# WFT0420CZ15_conv.net
KiCad netlist of a schematic drawn in EAGLE
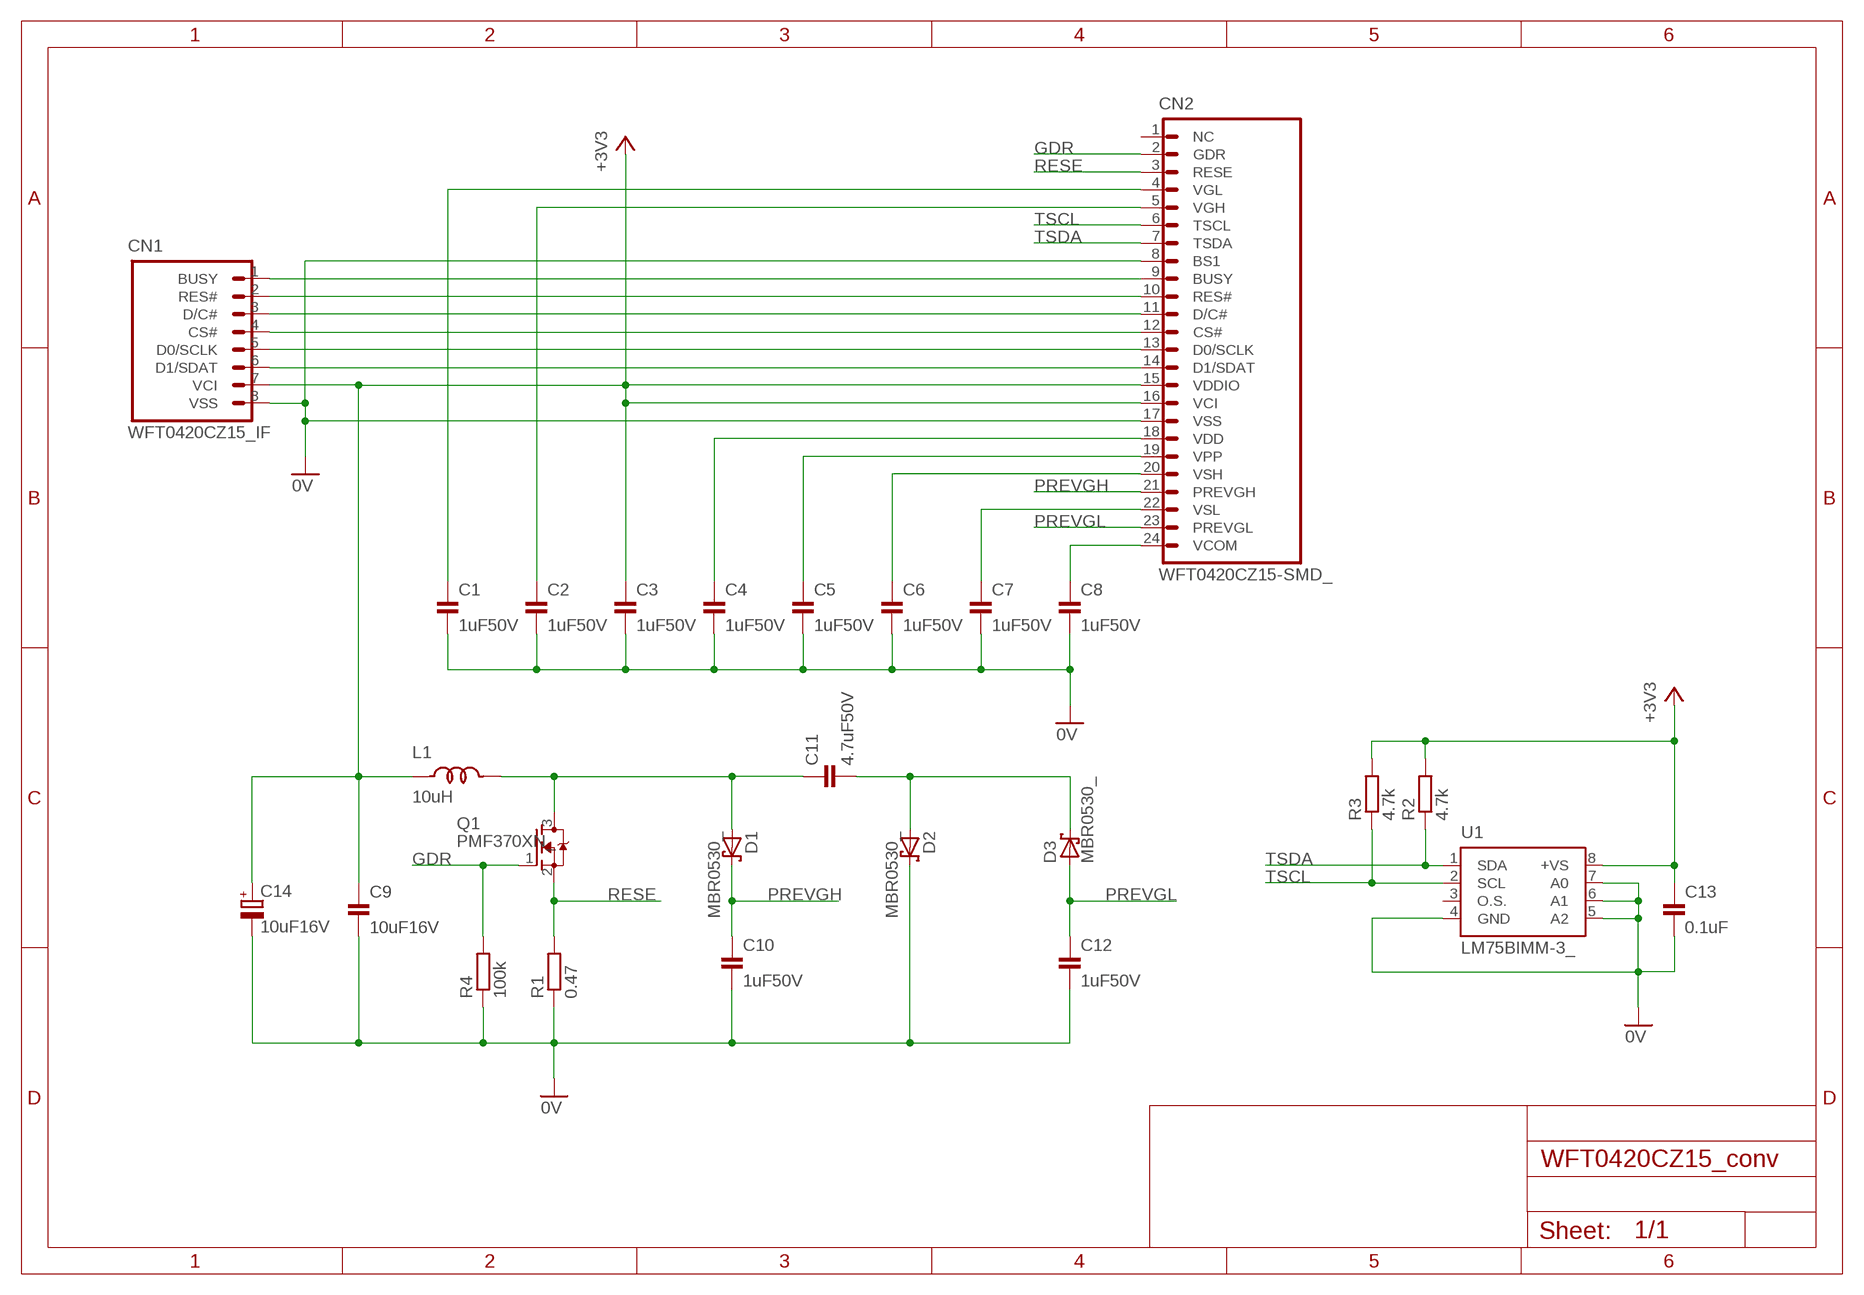
[diagram p0: schematic, sheet 1]

(export (version "E")
  (design (tool "Eeschema 10.0.6"))
  (components
    (comp (ref "C1")
      (value "1uF50V")
      (footprint "eagle-import:SMD_2012")
      (libsource (lib "eagle-import") (part "CAP_0805"))
    )
    (comp (ref "C2")
      (value "1uF50V")
      (footprint "eagle-import:SMD_2012")
      (libsource (lib "eagle-import") (part "CAP_0805"))
    )
    (comp (ref "C3")
      (value "1uF50V")
      (footprint "eagle-import:SMD_2012")
      (libsource (lib "eagle-import") (part "CAP_0805"))
    )
    (comp (ref "C4")
      (value "1uF50V")
      (footprint "eagle-import:SMD_2012")
      (libsource (lib "eagle-import") (part "CAP_0805"))
    )
    (comp (ref "C5")
      (value "1uF50V")
      (footprint "eagle-import:SMD_2012")
      (libsource (lib "eagle-import") (part "CAP_0805"))
    )
    (comp (ref "C6")
      (value "1uF50V")
      (footprint "eagle-import:SMD_2012")
      (libsource (lib "eagle-import") (part "CAP_0805"))
    )
    (comp (ref "C7")
      (value "1uF50V")
      (footprint "eagle-import:SMD_2012")
      (libsource (lib "eagle-import") (part "CAP_0805"))
    )
    (comp (ref "C8")
      (value "1uF50V")
      (footprint "eagle-import:SMD_2012")
      (libsource (lib "eagle-import") (part "CAP_0805"))
    )
    (comp (ref "C9")
      (value "10uF16V")
      (footprint "eagle-import:SMD_2012")
      (libsource (lib "eagle-import") (part "CAP_0805"))
    )
    (comp (ref "C10")
      (value "1uF50V")
      (footprint "eagle-import:SMD_2012")
      (libsource (lib "eagle-import") (part "CAP_0805"))
    )
    (comp (ref "C11")
      (value "4.7uF50V")
      (footprint "eagle-import:SMD_2012")
      (libsource (lib "eagle-import") (part "CAP_0805"))
    )
    (comp (ref "C12")
      (value "1uF50V")
      (footprint "eagle-import:SMD_2012")
      (libsource (lib "eagle-import") (part "CAP_0805"))
    )
    (comp (ref "C13")
      (value "0.1uF")
      (footprint "eagle-import:SMD_2012")
      (libsource (lib "eagle-import") (part "CAP_0805"))
    )
    (comp (ref "C14")
      (value "10uF16V")
      (footprint "eagle-import:C1210_TPST")
      (libsource (lib "eagle-import") (part "TPST106K016R0800"))
    )
    (comp (ref "CN1")
      (value "WFT0420CZ15_IF")
      (footprint "eagle-import:WFT0420CZ15_IF_8PIN")
      (libsource (lib "eagle-import") (part "WFT0420CZ15_IF"))
    )
    (comp (ref "CN2")
      (value "WFT0420CZ15-SMD_")
      (footprint "eagle-import:FH12A-24S-0.5SH_DEV")
      (libsource (lib "eagle-import") (part "WFT0420CZ15-SMD_"))
    )
    (comp (ref "D1")
      (value "MBR0530_")
      (footprint "eagle-import:MBR0530_DEV")
      (libsource (lib "eagle-import") (part "MBR0530_"))
    )
    (comp (ref "D2")
      (value "MBR0530_")
      (footprint "eagle-import:MBR0530_DEV")
      (libsource (lib "eagle-import") (part "MBR0530_"))
    )
    (comp (ref "D3")
      (value "MBR0530_")
      (footprint "eagle-import:MBR0530_DEV")
      (libsource (lib "eagle-import") (part "MBR0530_"))
    )
    (comp (ref "L1")
      (value "10uH")
      (footprint "eagle-import:NLCV25T")
      (libsource (lib "eagle-import") (part "NLCV25T"))
    )
    (comp (ref "Q1")
      (value "PMF370XN_")
      (footprint "eagle-import:SOT323_DEV")
      (libsource (lib "eagle-import") (part "PMF370XN_"))
    )
    (comp (ref "R1")
      (value "0.47")
      (footprint "eagle-import:SMD_2012")
      (libsource (lib "eagle-import") (part "RESISTOR_0805"))
    )
    (comp (ref "R2")
      (value "4.7k")
      (footprint "eagle-import:SMD_2012")
      (libsource (lib "eagle-import") (part "RESISTOR_0805"))
    )
    (comp (ref "R3")
      (value "4.7k")
      (footprint "eagle-import:SMD_2012")
      (libsource (lib "eagle-import") (part "RESISTOR_0805"))
    )
    (comp (ref "R4")
      (value "100k")
      (footprint "eagle-import:SMD_2012")
      (libsource (lib "eagle-import") (part "RESISTOR_0805"))
    )
    (comp (ref "U1")
      (value "LM75BIMM-3_")
      (footprint "eagle-import:SSOP8-DGK_DEV")
      (libsource (lib "eagle-import") (part "LM75BIMM-3_"))
    )
  )
  (nets
    (net (code "1") (name "+3V3") (class "Default")
      (node (ref "C13") (pin "1") (pinfunction "1_1") (pintype "passive"))
      (node (ref "C14") (pin "1") (pinfunction "+_1") (pintype "passive"))
      (node (ref "C3") (pin "1") (pinfunction "1_1") (pintype "passive"))
      (node (ref "C9") (pin "1") (pinfunction "1_1") (pintype "passive"))
      (node (ref "CN1") (pin "7") (pinfunction "VCI_7") (pintype "passive"))
      (node (ref "CN2") (pin "15") (pinfunction "VDDIO_15") (pintype "passive"))
      (node (ref "CN2") (pin "16") (pinfunction "VCI_16") (pintype "passive"))
      (node (ref "L1") (pin "1") (pinfunction "1_1") (pintype "passive"))
      (node (ref "R2") (pin "2") (pinfunction "2_2") (pintype "passive"))
      (node (ref "R3") (pin "2") (pinfunction "2_2") (pintype "passive"))
      (node (ref "U1") (pin "8") (pinfunction "+VS_8") (pintype "passive"))
    )
    (net (code "2") (name "/GDR") (class "Default")
      (node (ref "CN2") (pin "2") (pinfunction "GDR_2") (pintype "bidirectional"))
      (node (ref "Q1") (pin "1") (pinfunction "G_1") (pintype "passive"))
      (node (ref "R4") (pin "2") (pinfunction "2_2") (pintype "passive"))
    )
    (net (code "3") (name "/PREVGH") (class "Default")
      (node (ref "C10") (pin "1") (pinfunction "1_1") (pintype "passive"))
      (node (ref "CN2") (pin "21") (pinfunction "PREVGH_21") (pintype "passive"))
      (node (ref "D1") (pin "1") (pinfunction "C_1") (pintype "passive"))
    )
    (net (code "4") (name "/PREVGL") (class "Default")
      (node (ref "C12") (pin "1") (pinfunction "1_1") (pintype "passive"))
      (node (ref "CN2") (pin "23") (pinfunction "PREVGL_23") (pintype "passive"))
      (node (ref "D3") (pin "2") (pinfunction "A_2") (pintype "passive"))
    )
    (net (code "5") (name "/RESE") (class "Default")
      (node (ref "CN2") (pin "3") (pinfunction "RESE_3") (pintype "bidirectional"))
      (node (ref "Q1") (pin "2") (pinfunction "S_2") (pintype "passive"))
      (node (ref "R1") (pin "2") (pinfunction "2_2") (pintype "passive"))
    )
    (net (code "6") (name "/TSCL") (class "Default")
      (node (ref "CN2") (pin "6") (pinfunction "TSCL_6") (pintype "bidirectional"))
      (node (ref "R3") (pin "1") (pinfunction "1_1") (pintype "passive"))
      (node (ref "U1") (pin "2") (pinfunction "SCL_2") (pintype "bidirectional"))
    )
    (net (code "7") (name "/TSDA") (class "Default")
      (node (ref "CN2") (pin "7") (pinfunction "TSDA_7") (pintype "bidirectional"))
      (node (ref "R2") (pin "1") (pinfunction "1_1") (pintype "passive"))
      (node (ref "U1") (pin "1") (pinfunction "SDA_1") (pintype "bidirectional"))
    )
    (net (code "8") (name "0V") (class "Default")
      (node (ref "C1") (pin "2") (pinfunction "2_2") (pintype "passive"))
      (node (ref "C10") (pin "2") (pinfunction "2_2") (pintype "passive"))
      (node (ref "C12") (pin "2") (pinfunction "2_2") (pintype "passive"))
      (node (ref "C13") (pin "2") (pinfunction "2_2") (pintype "passive"))
      (node (ref "C14") (pin "2") (pinfunction "-_2") (pintype "passive"))
      (node (ref "C2") (pin "2") (pinfunction "2_2") (pintype "passive"))
      (node (ref "C3") (pin "2") (pinfunction "2_2") (pintype "passive"))
      (node (ref "C4") (pin "2") (pinfunction "2_2") (pintype "passive"))
      (node (ref "C5") (pin "2") (pinfunction "2_2") (pintype "passive"))
      (node (ref "C6") (pin "2") (pinfunction "2_2") (pintype "passive"))
      (node (ref "C7") (pin "2") (pinfunction "2_2") (pintype "passive"))
      (node (ref "C8") (pin "2") (pinfunction "2_2") (pintype "passive"))
      (node (ref "C9") (pin "2") (pinfunction "2_2") (pintype "passive"))
      (node (ref "CN1") (pin "8") (pinfunction "VSS_8") (pintype "passive"))
      (node (ref "CN2") (pin "17") (pinfunction "VSS_17") (pintype "passive"))
      (node (ref "CN2") (pin "8") (pinfunction "BS1_8") (pintype "bidirectional"))
      (node (ref "D2") (pin "1") (pinfunction "C_1") (pintype "passive"))
      (node (ref "R1") (pin "1") (pinfunction "1_1") (pintype "passive"))
      (node (ref "R4") (pin "1") (pinfunction "1_1") (pintype "passive"))
      (node (ref "U1") (pin "4") (pinfunction "GND_4") (pintype "passive"))
      (node (ref "U1") (pin "5") (pinfunction "A2_5") (pintype "bidirectional"))
      (node (ref "U1") (pin "6") (pinfunction "A1_6") (pintype "bidirectional"))
      (node (ref "U1") (pin "7") (pinfunction "A0_7") (pintype "bidirectional"))
    )
    (net (code "9") (name "Net-(CN1-BUSY)") (class "Default")
      (node (ref "CN1") (pin "1") (pinfunction "BUSY_1") (pintype "bidirectional"))
      (node (ref "CN2") (pin "9") (pinfunction "BUSY_9") (pintype "bidirectional"))
    )
    (net (code "10") (name "Net-(CN1-CS#)") (class "Default")
      (node (ref "CN1") (pin "4") (pinfunction "CS#_4") (pintype "bidirectional"))
      (node (ref "CN2") (pin "12") (pinfunction "CS#_12") (pintype "bidirectional"))
    )
    (net (code "11") (name "Net-(CN1-D0{slash}SCLK)") (class "Default")
      (node (ref "CN1") (pin "5") (pinfunction "D0/SCLK_5") (pintype "bidirectional"))
      (node (ref "CN2") (pin "13") (pinfunction "D0/SCLK_13") (pintype "bidirectional"))
    )
    (net (code "12") (name "Net-(CN1-D1{slash}SDAT)") (class "Default")
      (node (ref "CN1") (pin "6") (pinfunction "D1/SDAT_6") (pintype "bidirectional"))
      (node (ref "CN2") (pin "14") (pinfunction "D1/SDAT_14") (pintype "bidirectional"))
    )
    (net (code "13") (name "Net-(CN1-D{slash}C#)") (class "Default")
      (node (ref "CN1") (pin "3") (pinfunction "D/C#_3") (pintype "bidirectional"))
      (node (ref "CN2") (pin "11") (pinfunction "D/C#_11") (pintype "bidirectional"))
    )
    (net (code "14") (name "Net-(CN1-RES#)") (class "Default")
      (node (ref "CN1") (pin "2") (pinfunction "RES#_2") (pintype "bidirectional"))
      (node (ref "CN2") (pin "10") (pinfunction "RES#_10") (pintype "bidirectional"))
    )
    (net (code "15") (name "Net-(CN2-VCOM)") (class "Default")
      (node (ref "C8") (pin "1") (pinfunction "1_1") (pintype "passive"))
      (node (ref "CN2") (pin "24") (pinfunction "VCOM_24") (pintype "passive"))
    )
    (net (code "16") (name "Net-(CN2-VDD)") (class "Default")
      (node (ref "C4") (pin "1") (pinfunction "1_1") (pintype "passive"))
      (node (ref "CN2") (pin "18") (pinfunction "VDD_18") (pintype "passive"))
    )
    (net (code "17") (name "Net-(CN2-VGH)") (class "Default")
      (node (ref "C2") (pin "1") (pinfunction "1_1") (pintype "passive"))
      (node (ref "CN2") (pin "5") (pinfunction "VGH_5") (pintype "passive"))
    )
    (net (code "18") (name "Net-(CN2-VGL)") (class "Default")
      (node (ref "C1") (pin "1") (pinfunction "1_1") (pintype "passive"))
      (node (ref "CN2") (pin "4") (pinfunction "VGL_4") (pintype "passive"))
    )
    (net (code "19") (name "Net-(CN2-VPP)") (class "Default")
      (node (ref "C5") (pin "1") (pinfunction "1_1") (pintype "passive"))
      (node (ref "CN2") (pin "19") (pinfunction "VPP_19") (pintype "passive"))
    )
    (net (code "20") (name "Net-(CN2-VSH)") (class "Default")
      (node (ref "C6") (pin "1") (pinfunction "1_1") (pintype "passive"))
      (node (ref "CN2") (pin "20") (pinfunction "VSH_20") (pintype "passive"))
    )
    (net (code "21") (name "Net-(CN2-VSL)") (class "Default")
      (node (ref "C7") (pin "1") (pinfunction "1_1") (pintype "passive"))
      (node (ref "CN2") (pin "22") (pinfunction "VSL_22") (pintype "passive"))
    )
    (net (code "22") (name "Net-(D1-A)") (class "Default")
      (node (ref "C11") (pin "1") (pinfunction "1_1") (pintype "passive"))
      (node (ref "D1") (pin "2") (pinfunction "A_2") (pintype "passive"))
      (node (ref "L1") (pin "2") (pinfunction "2_2") (pintype "passive"))
      (node (ref "Q1") (pin "3") (pinfunction "D_3") (pintype "passive"))
    )
    (net (code "23") (name "Net-(D2-A)") (class "Default")
      (node (ref "C11") (pin "2") (pinfunction "2_2") (pintype "passive"))
      (node (ref "D2") (pin "2") (pinfunction "A_2") (pintype "passive"))
      (node (ref "D3") (pin "1") (pinfunction "C_1") (pintype "passive"))
    )
    (net (code "24") (name "unconnected-(CN2-NC-Pad1)") (class "Default")
      (node (ref "CN2") (pin "1") (pinfunction "NC_1") (pintype "no_connect"))
    )
    (net (code "25") (name "unconnected-(U1-O.S.-Pad3)") (class "Default")
      (node (ref "U1") (pin "3") (pinfunction "O.S._3") (pintype "bidirectional"))
    )
  )
)
